# VGA32_V3.net
KiCad netlist of a schematic drawn in EAGLE
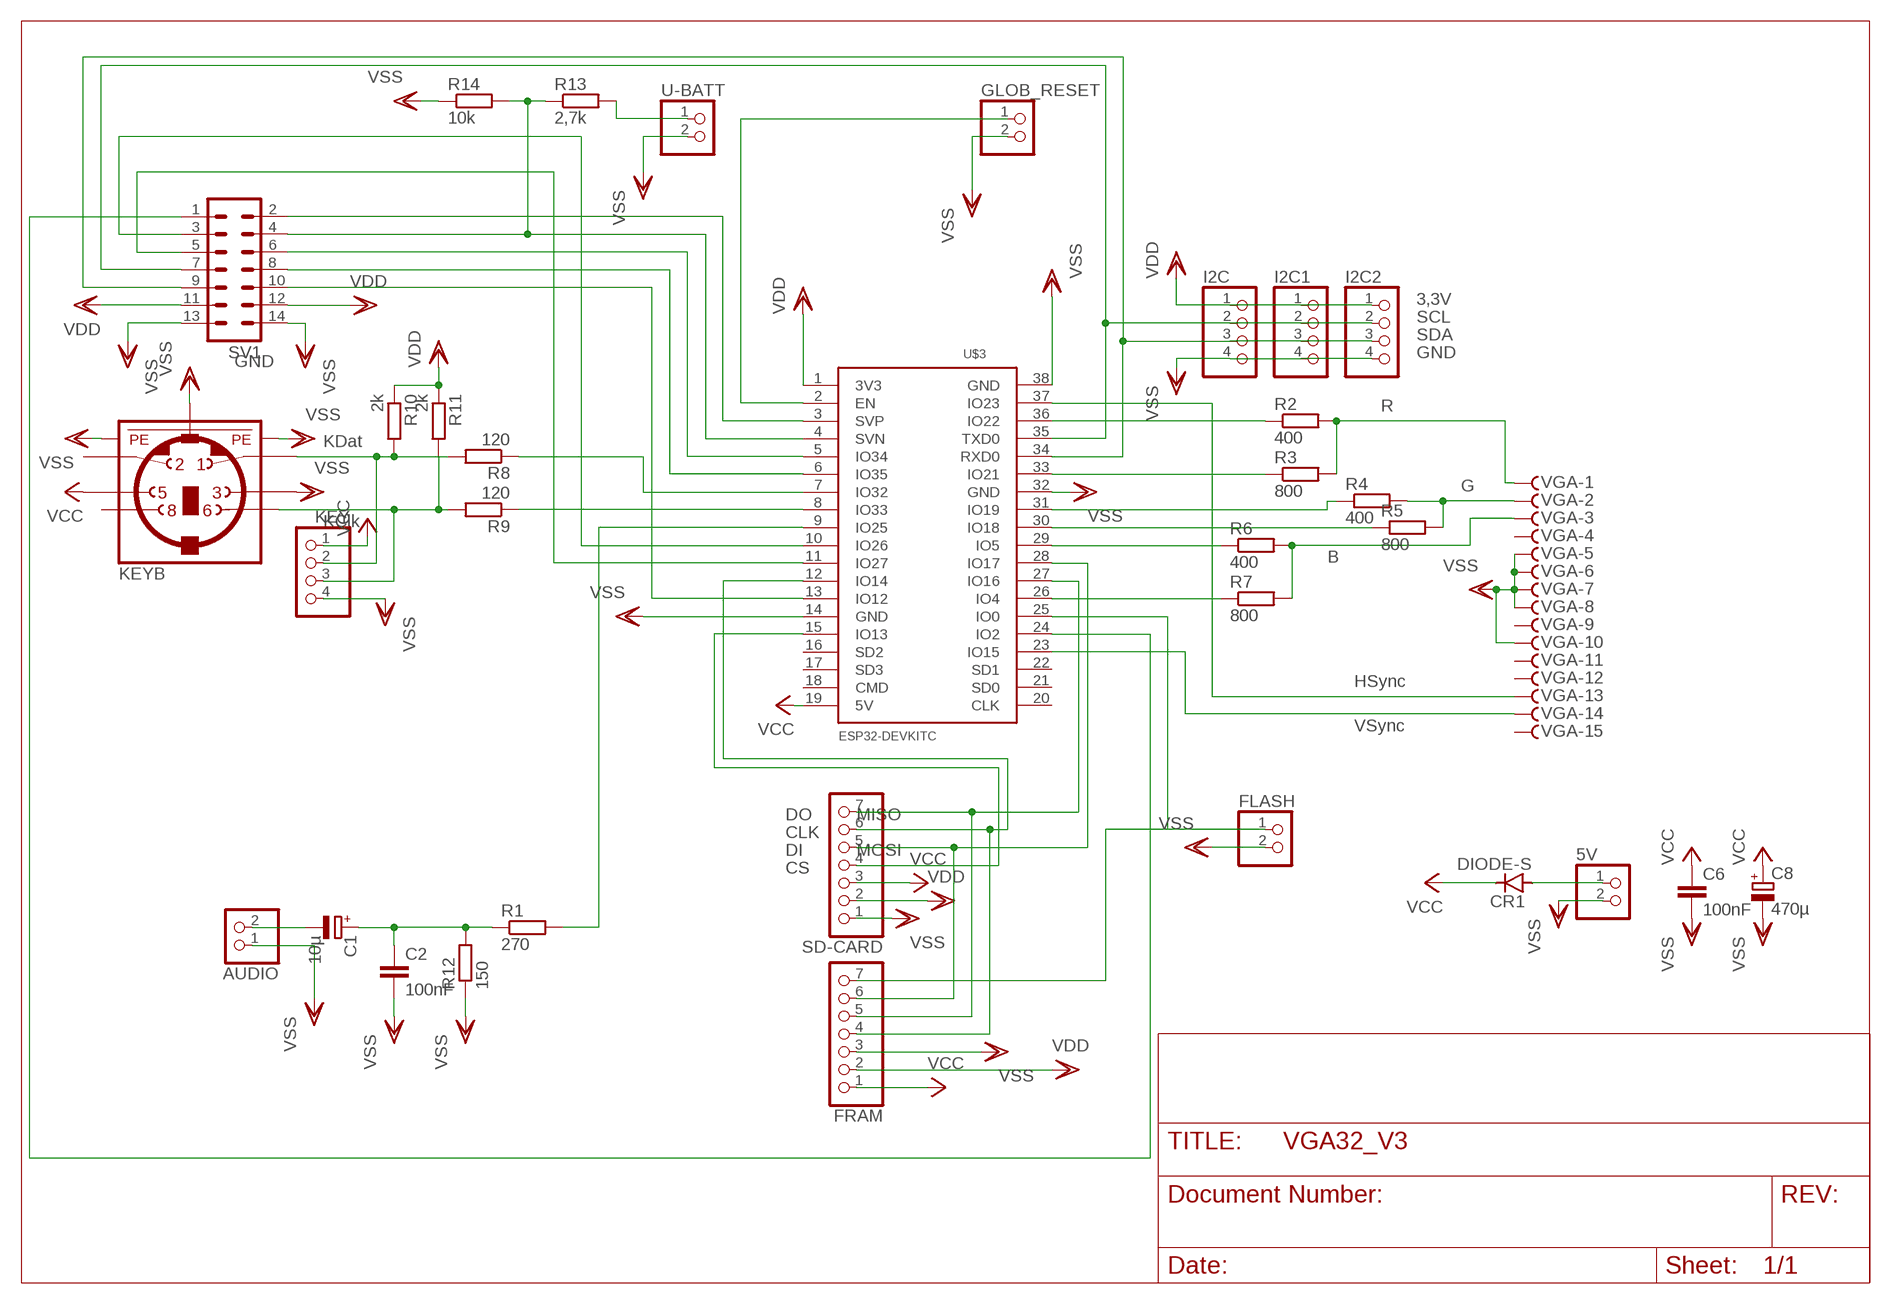
[diagram p0: schematic, sheet 1]

(export (version "E")
  (design (tool "Eeschema 10.0.6"))
  (components
    (comp (ref "5V")
      (value "PINHD-1X2")
      (footprint "eagle-import:1X02")
      (libsource (lib "eagle-import") (part "PINHD-1X2"))
    )
    (comp (ref "AUDIO")
      (value "PINHD-1X2")
      (footprint "eagle-import:1X02")
      (libsource (lib "eagle-import") (part "PINHD-1X2"))
    )
    (comp (ref "C1")
      (value "10µ")
      (footprint "eagle-import:E2-4")
      (libsource (lib "eagle-import") (part "CPOL-EUE2-4"))
    )
    (comp (ref "C2")
      (value "100nF")
      (footprint "eagle-import:C025-030X050")
      (libsource (lib "eagle-import") (part "C-EU025-030X050"))
    )
    (comp (ref "C6")
      (value "100nF")
      (footprint "eagle-import:C025-030X050")
      (libsource (lib "eagle-import") (part "C-EU025-030X050"))
    )
    (comp (ref "C8")
      (value "470µ")
      (footprint "eagle-import:E3,5-10")
      (libsource (lib "eagle-import") (part "CPOL-EUE3.5-10"))
    )
    (comp (ref "CR1")
      (value "DIODE-S")
      (footprint "eagle-import:DO35-10")
      (libsource (lib "eagle-import") (part "DIODE-S"))
    )
    (comp (ref "FLASH")
      (value "PINHD-1X2")
      (footprint "eagle-import:1X02")
      (libsource (lib "eagle-import") (part "PINHD-1X2"))
    )
    (comp (ref "FRAM")
      (value "PINHD-1X7")
      (footprint "eagle-import:1X07")
      (libsource (lib "eagle-import") (part "PINHD-1X7"))
    )
    (comp (ref "GLOB_RESET")
      (value "PINHD-1X2")
      (footprint "eagle-import:1X02")
      (libsource (lib "eagle-import") (part "PINHD-1X2"))
    )
    (comp (ref "I2C")
      (value "PINHD-1X4")
      (footprint "eagle-import:1X04")
      (libsource (lib "eagle-import") (part "PINHD-1X4"))
    )
    (comp (ref "I2C1")
      (value "PINHD-1X4")
      (footprint "eagle-import:1X04")
      (libsource (lib "eagle-import") (part "PINHD-1X4"))
    )
    (comp (ref "I2C2")
      (value "PINHD-1X4")
      (footprint "eagle-import:1X04")
      (libsource (lib "eagle-import") (part "PINHD-1X4"))
    )
    (comp (ref "KEY")
      (value "PINHD-1X4")
      (footprint "eagle-import:1X04")
      (libsource (lib "eagle-import") (part "PINHD-1X4"))
    )
    (comp (ref "KEYB")
      (value "MINI_DIN_6")
      (footprint "eagle-import:M_DIN6")
      (libsource (lib "eagle-import") (part "MINI_DIN_6"))
    )
    (comp (ref "R1")
      (value "270")
      (footprint "eagle-import:0204_7")
      (libsource (lib "eagle-import") (part "R-EU_0204/7"))
    )
    (comp (ref "R2")
      (value "400")
      (footprint "eagle-import:0204_7")
      (libsource (lib "eagle-import") (part "R-EU_0204/7"))
    )
    (comp (ref "R3")
      (value "800")
      (footprint "eagle-import:0204_7")
      (libsource (lib "eagle-import") (part "R-EU_0204/7"))
    )
    (comp (ref "R4")
      (value "400")
      (footprint "eagle-import:0204_7")
      (libsource (lib "eagle-import") (part "R-EU_0204/7"))
    )
    (comp (ref "R5")
      (value "800")
      (footprint "eagle-import:0204_7")
      (libsource (lib "eagle-import") (part "R-EU_0204/7"))
    )
    (comp (ref "R6")
      (value "400")
      (footprint "eagle-import:0204_7")
      (libsource (lib "eagle-import") (part "R-EU_0204/7"))
    )
    (comp (ref "R7")
      (value "800")
      (footprint "eagle-import:0204_7")
      (libsource (lib "eagle-import") (part "R-EU_0204/7"))
    )
    (comp (ref "R8")
      (value "120")
      (footprint "eagle-import:0204_7")
      (libsource (lib "eagle-import") (part "R-EU_0204/7"))
    )
    (comp (ref "R9")
      (value "120")
      (footprint "eagle-import:0204_7")
      (libsource (lib "eagle-import") (part "R-EU_0204/7"))
    )
    (comp (ref "R10")
      (value "2k")
      (footprint "eagle-import:0204_7")
      (libsource (lib "eagle-import") (part "R-EU_0204/7"))
    )
    (comp (ref "R11")
      (value "2k")
      (footprint "eagle-import:0204_7")
      (libsource (lib "eagle-import") (part "R-EU_0204/7"))
    )
    (comp (ref "R12")
      (value "150")
      (footprint "eagle-import:0204_7")
      (libsource (lib "eagle-import") (part "R-EU_0204/7"))
    )
    (comp (ref "R13")
      (value "2,7k")
      (footprint "eagle-import:0204_7")
      (libsource (lib "eagle-import") (part "R-EU_0204/7"))
    )
    (comp (ref "R14")
      (value "10k")
      (footprint "eagle-import:0204_7")
      (libsource (lib "eagle-import") (part "R-EU_0204/7"))
    )
    (comp (ref "SD-CARD")
      (value "PINHD-1X7")
      (footprint "eagle-import:1X07")
      (libsource (lib "eagle-import") (part "PINHD-1X7"))
    )
    (comp (ref "SV1")
      (value "ML14L")
      (footprint "eagle-import:ML14L")
      (libsource (lib "eagle-import") (part "ML14L"))
    )
    (comp (ref "U$3")
      (value "ESP32DEVKITC")
      (footprint "eagle-import:ESP32-DEVKITC")
      (libsource (lib "eagle-import") (part "ESP32DEVKITC"))
    )
    (comp (ref "U-BATT")
      (value "PINHD-1X2")
      (footprint "eagle-import:1X02")
      (libsource (lib "eagle-import") (part "PINHD-1X2"))
    )
    (comp (ref "VGA")
      (value "F15HDHS")
      (footprint "eagle-import:HDF15H")
      (libsource (lib "eagle-import") (part "F15?SHDH"))
    )
  )
  (nets
    (net (code "1") (name "Net-(5V-Pad1)") (class "Default")
      (node (ref "5V") (pin "1") (pinfunction "1_1") (pintype "passive"))
      (node (ref "CR1") (pin "A") (pinfunction "A_A") (pintype "passive"))
    )
    (net (code "2") (name "Net-(AUDIO-Pad2)") (class "Default")
      (node (ref "AUDIO") (pin "2") (pinfunction "2_2") (pintype "passive"))
      (node (ref "C1") (pin "-") (pinfunction "-_-") (pintype "passive"))
    )
    (net (code "3") (name "Net-(C1-Pad+)") (class "Default")
      (node (ref "C1") (pin "+") (pinfunction "+_+") (pintype "passive"))
      (node (ref "C2") (pin "1") (pinfunction "1_1") (pintype "passive"))
      (node (ref "R1") (pin "1") (pinfunction "1_1") (pintype "passive"))
      (node (ref "R12") (pin "2") (pinfunction "2_2") (pintype "passive"))
    )
    (net (code "4") (name "Net-(KEY-Pad2)") (class "Default")
      (node (ref "KEY") (pin "2") (pinfunction "2_2") (pintype "passive"))
      (node (ref "KEYB") (pin "1") (pinfunction "1_1") (pintype "passive"))
      (node (ref "R10") (pin "2") (pinfunction "2_2") (pintype "passive"))
      (node (ref "R8") (pin "2") (pinfunction "2_2") (pintype "passive"))
    )
    (net (code "5") (name "Net-(KEY-Pad3)") (class "Default")
      (node (ref "KEY") (pin "3") (pinfunction "3_3") (pintype "passive"))
      (node (ref "KEYB") (pin "6") (pinfunction "6_6") (pintype "passive"))
      (node (ref "R11") (pin "2") (pinfunction "2_2") (pintype "passive"))
      (node (ref "R9") (pin "2") (pinfunction "2_2") (pintype "passive"))
    )
    (net (code "6") (name "Net-(R13-Pad2)") (class "Default")
      (node (ref "R13") (pin "2") (pinfunction "2_2") (pintype "passive"))
      (node (ref "U-BATT") (pin "1") (pinfunction "1_1") (pintype "passive"))
    )
    (net (code "7") (name "Net-(U$3-EN)") (class "Default")
      (node (ref "GLOB_RESET") (pin "1") (pinfunction "1_1") (pintype "passive"))
      (node (ref "U$3") (pin "2") (pinfunction "EN_2") (pintype "bidirectional"))
    )
    (net (code "8") (name "Net-(U$3-IO0)") (class "Default")
      (node (ref "FLASH") (pin "1") (pinfunction "1_1") (pintype "passive"))
      (node (ref "FRAM") (pin "7") (pinfunction "7_7") (pintype "passive"))
      (node (ref "U$3") (pin "25") (pinfunction "IO0_25") (pintype "bidirectional"))
    )
    (net (code "9") (name "Net-(U$3-IO2)") (class "Default")
      (node (ref "SV1") (pin "1") (pinfunction "1_1") (pintype "passive"))
      (node (ref "U$3") (pin "24") (pinfunction "IO2_24") (pintype "bidirectional"))
    )
    (net (code "10") (name "Net-(U$3-IO4)") (class "Default")
      (node (ref "R7") (pin "1") (pinfunction "1_1") (pintype "passive"))
      (node (ref "U$3") (pin "26") (pinfunction "IO4_26") (pintype "bidirectional"))
    )
    (net (code "11") (name "Net-(U$3-IO5)") (class "Default")
      (node (ref "R6") (pin "1") (pinfunction "1_1") (pintype "passive"))
      (node (ref "U$3") (pin "29") (pinfunction "IO5_29") (pintype "bidirectional"))
    )
    (net (code "12") (name "Net-(U$3-IO12)") (class "Default")
      (node (ref "SV1") (pin "10") (pinfunction "10_10") (pintype "passive"))
      (node (ref "U$3") (pin "13") (pinfunction "IO12_13") (pintype "bidirectional"))
    )
    (net (code "13") (name "Net-(U$3-IO13)") (class "Default")
      (node (ref "SD-CARD") (pin "4") (pinfunction "4_4") (pintype "passive"))
      (node (ref "U$3") (pin "15") (pinfunction "IO13_15") (pintype "bidirectional"))
    )
    (net (code "14") (name "Net-(U$3-IO14)") (class "Default")
      (node (ref "FRAM") (pin "4") (pinfunction "4_4") (pintype "passive"))
      (node (ref "SD-CARD") (pin "6") (pinfunction "6_6") (pintype "passive"))
      (node (ref "U$3") (pin "12") (pinfunction "IO14_12") (pintype "bidirectional"))
    )
    (net (code "15") (name "Net-(U$3-IO15)") (class "Default")
      (node (ref "U$3") (pin "23") (pinfunction "IO15_23") (pintype "bidirectional"))
      (node (ref "VGA") (pin "14") (pinfunction "F_14") (pintype "passive"))
    )
    (net (code "16") (name "Net-(U$3-IO16)") (class "Default")
      (node (ref "FRAM") (pin "5") (pinfunction "5_5") (pintype "passive"))
      (node (ref "SD-CARD") (pin "7") (pinfunction "7_7") (pintype "passive"))
      (node (ref "U$3") (pin "27") (pinfunction "IO16_27") (pintype "bidirectional"))
    )
    (net (code "17") (name "Net-(U$3-IO17)") (class "Default")
      (node (ref "FRAM") (pin "6") (pinfunction "6_6") (pintype "passive"))
      (node (ref "SD-CARD") (pin "5") (pinfunction "5_5") (pintype "passive"))
      (node (ref "U$3") (pin "28") (pinfunction "IO17_28") (pintype "bidirectional"))
    )
    (net (code "18") (name "Net-(U$3-IO18)") (class "Default")
      (node (ref "R5") (pin "1") (pinfunction "1_1") (pintype "passive"))
      (node (ref "U$3") (pin "30") (pinfunction "IO18_30") (pintype "bidirectional"))
    )
    (net (code "19") (name "Net-(U$3-IO19)") (class "Default")
      (node (ref "R4") (pin "1") (pinfunction "1_1") (pintype "passive"))
      (node (ref "U$3") (pin "31") (pinfunction "IO19_31") (pintype "bidirectional"))
    )
    (net (code "20") (name "Net-(U$3-IO21)") (class "Default")
      (node (ref "R3") (pin "1") (pinfunction "1_1") (pintype "passive"))
      (node (ref "U$3") (pin "33") (pinfunction "IO21_33") (pintype "bidirectional"))
    )
    (net (code "21") (name "Net-(U$3-IO22)") (class "Default")
      (node (ref "R2") (pin "1") (pinfunction "1_1") (pintype "passive"))
      (node (ref "U$3") (pin "36") (pinfunction "IO22_36") (pintype "bidirectional"))
    )
    (net (code "22") (name "Net-(U$3-IO23)") (class "Default")
      (node (ref "U$3") (pin "37") (pinfunction "IO23_37") (pintype "bidirectional"))
      (node (ref "VGA") (pin "13") (pinfunction "F_13") (pintype "passive"))
    )
    (net (code "23") (name "Net-(U$3-IO25)") (class "Default")
      (node (ref "R1") (pin "2") (pinfunction "2_2") (pintype "passive"))
      (node (ref "U$3") (pin "9") (pinfunction "IO25_9") (pintype "bidirectional"))
    )
    (net (code "24") (name "Net-(U$3-IO26)") (class "Default")
      (node (ref "SV1") (pin "3") (pinfunction "3_3") (pintype "passive"))
      (node (ref "U$3") (pin "10") (pinfunction "IO26_10") (pintype "bidirectional"))
    )
    (net (code "25") (name "Net-(U$3-IO27)") (class "Default")
      (node (ref "SV1") (pin "5") (pinfunction "5_5") (pintype "passive"))
      (node (ref "U$3") (pin "11") (pinfunction "IO27_11") (pintype "bidirectional"))
    )
    (net (code "26") (name "Net-(U$3-IO32)") (class "Default")
      (node (ref "R8") (pin "1") (pinfunction "1_1") (pintype "passive"))
      (node (ref "U$3") (pin "7") (pinfunction "IO32_7") (pintype "bidirectional"))
    )
    (net (code "27") (name "Net-(U$3-IO33)") (class "Default")
      (node (ref "R9") (pin "1") (pinfunction "1_1") (pintype "passive"))
      (node (ref "U$3") (pin "8") (pinfunction "IO33_8") (pintype "bidirectional"))
    )
    (net (code "28") (name "Net-(U$3-IO34)") (class "Default")
      (node (ref "SV1") (pin "6") (pinfunction "6_6") (pintype "passive"))
      (node (ref "U$3") (pin "5") (pinfunction "IO34_5") (pintype "bidirectional"))
    )
    (net (code "29") (name "Net-(U$3-IO35)") (class "Default")
      (node (ref "SV1") (pin "8") (pinfunction "8_8") (pintype "passive"))
      (node (ref "U$3") (pin "6") (pinfunction "IO35_6") (pintype "bidirectional"))
    )
    (net (code "30") (name "Net-(U$3-RXD0)") (class "Default")
      (node (ref "I2C") (pin "3") (pinfunction "3_3") (pintype "passive"))
      (node (ref "I2C1") (pin "3") (pinfunction "3_3") (pintype "passive"))
      (node (ref "I2C2") (pin "3") (pinfunction "3_3") (pintype "passive"))
      (node (ref "SV1") (pin "9") (pinfunction "9_9") (pintype "passive"))
      (node (ref "U$3") (pin "34") (pinfunction "RXD0_34") (pintype "bidirectional"))
    )
    (net (code "31") (name "Net-(U$3-SVN)") (class "Default")
      (node (ref "R13") (pin "1") (pinfunction "1_1") (pintype "passive"))
      (node (ref "R14") (pin "2") (pinfunction "2_2") (pintype "passive"))
      (node (ref "SV1") (pin "4") (pinfunction "4_4") (pintype "passive"))
      (node (ref "U$3") (pin "4") (pinfunction "SVN_4") (pintype "bidirectional"))
    )
    (net (code "32") (name "Net-(U$3-SVP)") (class "Default")
      (node (ref "SV1") (pin "2") (pinfunction "2_2") (pintype "passive"))
      (node (ref "U$3") (pin "3") (pinfunction "SVP_3") (pintype "bidirectional"))
    )
    (net (code "33") (name "Net-(U$3-TXD0)") (class "Default")
      (node (ref "I2C") (pin "2") (pinfunction "2_2") (pintype "passive"))
      (node (ref "I2C1") (pin "2") (pinfunction "2_2") (pintype "passive"))
      (node (ref "I2C2") (pin "2") (pinfunction "2_2") (pintype "passive"))
      (node (ref "SV1") (pin "7") (pinfunction "7_7") (pintype "passive"))
      (node (ref "U$3") (pin "35") (pinfunction "TXD0_35") (pintype "bidirectional"))
    )
    (net (code "34") (name "Net-(VGAA-F)") (class "Default")
      (node (ref "R2") (pin "2") (pinfunction "2_2") (pintype "passive"))
      (node (ref "R3") (pin "2") (pinfunction "2_2") (pintype "passive"))
      (node (ref "VGA") (pin "1") (pinfunction "F_1") (pintype "passive"))
    )
    (net (code "35") (name "Net-(VGAH-F)") (class "Default")
      (node (ref "R4") (pin "2") (pinfunction "2_2") (pintype "passive"))
      (node (ref "R5") (pin "2") (pinfunction "2_2") (pintype "passive"))
      (node (ref "VGA") (pin "2") (pinfunction "F_2") (pintype "passive"))
    )
    (net (code "36") (name "Net-(VGAI-F)") (class "Default")
      (node (ref "R6") (pin "2") (pinfunction "2_2") (pintype "passive"))
      (node (ref "R7") (pin "2") (pinfunction "2_2") (pintype "passive"))
      (node (ref "VGA") (pin "3") (pinfunction "F_3") (pintype "passive"))
    )
    (net (code "37") (name "VCC") (class "Default")
      (node (ref "C6") (pin "1") (pinfunction "1_1") (pintype "passive"))
      (node (ref "C8") (pin "+") (pinfunction "+_+") (pintype "passive"))
      (node (ref "CR1") (pin "C") (pinfunction "C_C") (pintype "passive"))
      (node (ref "FRAM") (pin "1") (pinfunction "1_1") (pintype "passive"))
      (node (ref "KEY") (pin "1") (pinfunction "1_1") (pintype "passive"))
      (node (ref "KEYB") (pin "5") (pinfunction "5_5") (pintype "passive"))
      (node (ref "SD-CARD") (pin "3") (pinfunction "3_3") (pintype "passive"))
      (node (ref "U$3") (pin "19") (pinfunction "5V_19") (pintype "bidirectional"))
    )
    (net (code "38") (name "VDD") (class "Default")
      (node (ref "FRAM") (pin "2") (pinfunction "2_2") (pintype "passive"))
      (node (ref "I2C") (pin "1") (pinfunction "1_1") (pintype "passive"))
      (node (ref "I2C1") (pin "1") (pinfunction "1_1") (pintype "passive"))
      (node (ref "I2C2") (pin "1") (pinfunction "1_1") (pintype "passive"))
      (node (ref "R10") (pin "1") (pinfunction "1_1") (pintype "passive"))
      (node (ref "R11") (pin "1") (pinfunction "1_1") (pintype "passive"))
      (node (ref "SD-CARD") (pin "2") (pinfunction "2_2") (pintype "passive"))
      (node (ref "SV1") (pin "11") (pinfunction "11_11") (pintype "passive"))
      (node (ref "SV1") (pin "12") (pinfunction "12_12") (pintype "passive"))
      (node (ref "U$3") (pin "1") (pinfunction "3V3_1") (pintype "bidirectional"))
    )
    (net (code "39") (name "VSS") (class "Default")
      (node (ref "5V") (pin "2") (pinfunction "2_2") (pintype "passive"))
      (node (ref "AUDIO") (pin "1") (pinfunction "1_1") (pintype "passive"))
      (node (ref "C2") (pin "2") (pinfunction "2_2") (pintype "passive"))
      (node (ref "C6") (pin "2") (pinfunction "2_2") (pintype "passive"))
      (node (ref "C8") (pin "-") (pinfunction "-_-") (pintype "passive"))
      (node (ref "FLASH") (pin "2") (pinfunction "2_2") (pintype "passive"))
      (node (ref "FRAM") (pin "3") (pinfunction "3_3") (pintype "passive"))
      (node (ref "GLOB_RESET") (pin "2") (pinfunction "2_2") (pintype "passive"))
      (node (ref "I2C") (pin "4") (pinfunction "4_4") (pintype "passive"))
      (node (ref "I2C1") (pin "4") (pinfunction "4_4") (pintype "passive"))
      (node (ref "I2C2") (pin "4") (pinfunction "4_4") (pintype "passive"))
      (node (ref "KEY") (pin "4") (pinfunction "4_4") (pintype "passive"))
      (node (ref "KEYB") (pin "3") (pinfunction "3_3") (pintype "passive"))
      (node (ref "KEYB") (pin "SH1") (pinfunction "PE1_SH1") (pintype "power_in"))
      (node (ref "KEYB") (pin "SH2") (pinfunction "PE2_SH2") (pintype "power_in"))
      (node (ref "KEYB") (pin "SH3") (pinfunction "PE3_SH3") (pintype "power_in"))
      (node (ref "R12") (pin "1") (pinfunction "1_1") (pintype "passive"))
      (node (ref "R14") (pin "1") (pinfunction "1_1") (pintype "passive"))
      (node (ref "SD-CARD") (pin "1") (pinfunction "1_1") (pintype "passive"))
      (node (ref "SV1") (pin "13") (pinfunction "13_13") (pintype "passive"))
      (node (ref "SV1") (pin "14") (pinfunction "14_14") (pintype "passive"))
      (node (ref "U$3") (pin "14") (pinfunction "GND_14") (pintype "bidirectional"))
      (node (ref "U$3") (pin "32") (pinfunction "GND_32") (pintype "bidirectional"))
      (node (ref "U$3") (pin "38") (pinfunction "GND_38") (pintype "bidirectional"))
      (node (ref "U-BATT") (pin "2") (pinfunction "2_2") (pintype "passive"))
      (node (ref "VGA") (pin "10") (pinfunction "F_10") (pintype "passive"))
      (node (ref "VGA") (pin "5") (pinfunction "F_5") (pintype "passive"))
      (node (ref "VGA") (pin "6") (pinfunction "F_6") (pintype "passive"))
      (node (ref "VGA") (pin "7") (pinfunction "F_7") (pintype "passive"))
      (node (ref "VGA") (pin "8") (pinfunction "F_8") (pintype "passive"))
    )
    (net (code "40") (name "unconnected-(KEYB-Pad2)") (class "Default")
      (node (ref "KEYB") (pin "2") (pinfunction "2_2") (pintype "passive"))
    )
    (net (code "41") (name "unconnected-(KEYB-Pad8)") (class "Default")
      (node (ref "KEYB") (pin "8") (pinfunction "8_8") (pintype "passive"))
    )
    (net (code "42") (name "unconnected-(U$3-CLK-Pad20)") (class "Default")
      (node (ref "U$3") (pin "20") (pinfunction "CLK_20") (pintype "bidirectional"))
    )
    (net (code "43") (name "unconnected-(U$3-CMD-Pad18)") (class "Default")
      (node (ref "U$3") (pin "18") (pinfunction "CMD_18") (pintype "bidirectional"))
    )
    (net (code "44") (name "unconnected-(U$3-SD0-Pad21)") (class "Default")
      (node (ref "U$3") (pin "21") (pinfunction "SD0_21") (pintype "bidirectional"))
    )
    (net (code "45") (name "unconnected-(U$3-SD1-Pad22)") (class "Default")
      (node (ref "U$3") (pin "22") (pinfunction "SD1_22") (pintype "bidirectional"))
    )
    (net (code "46") (name "unconnected-(U$3-SD2-Pad16)") (class "Default")
      (node (ref "U$3") (pin "16") (pinfunction "SD2_16") (pintype "bidirectional"))
    )
    (net (code "47") (name "unconnected-(U$3-SD3-Pad17)") (class "Default")
      (node (ref "U$3") (pin "17") (pinfunction "SD3_17") (pintype "bidirectional"))
    )
    (net (code "48") (name "unconnected-(VGAC-F-Pad11)") (class "Default")
      (node (ref "VGA") (pin "11") (pinfunction "F_11") (pintype "passive"))
    )
    (net (code "49") (name "unconnected-(VGAD-F-Pad12)") (class "Default")
      (node (ref "VGA") (pin "12") (pinfunction "F_12") (pintype "passive"))
    )
    (net (code "50") (name "unconnected-(VGAG-F-Pad15)") (class "Default")
      (node (ref "VGA") (pin "15") (pinfunction "F_15") (pintype "passive"))
    )
    (net (code "51") (name "unconnected-(VGAJ-F-Pad4)") (class "Default")
      (node (ref "VGA") (pin "4") (pinfunction "F_4") (pintype "passive"))
    )
    (net (code "52") (name "unconnected-(VGAO-F-Pad9)") (class "Default")
      (node (ref "VGA") (pin "9") (pinfunction "F_9") (pintype "passive"))
    )
  )
)
